# adalogger_featherwing.net
KiCad netlist of a schematic drawn in EAGLE
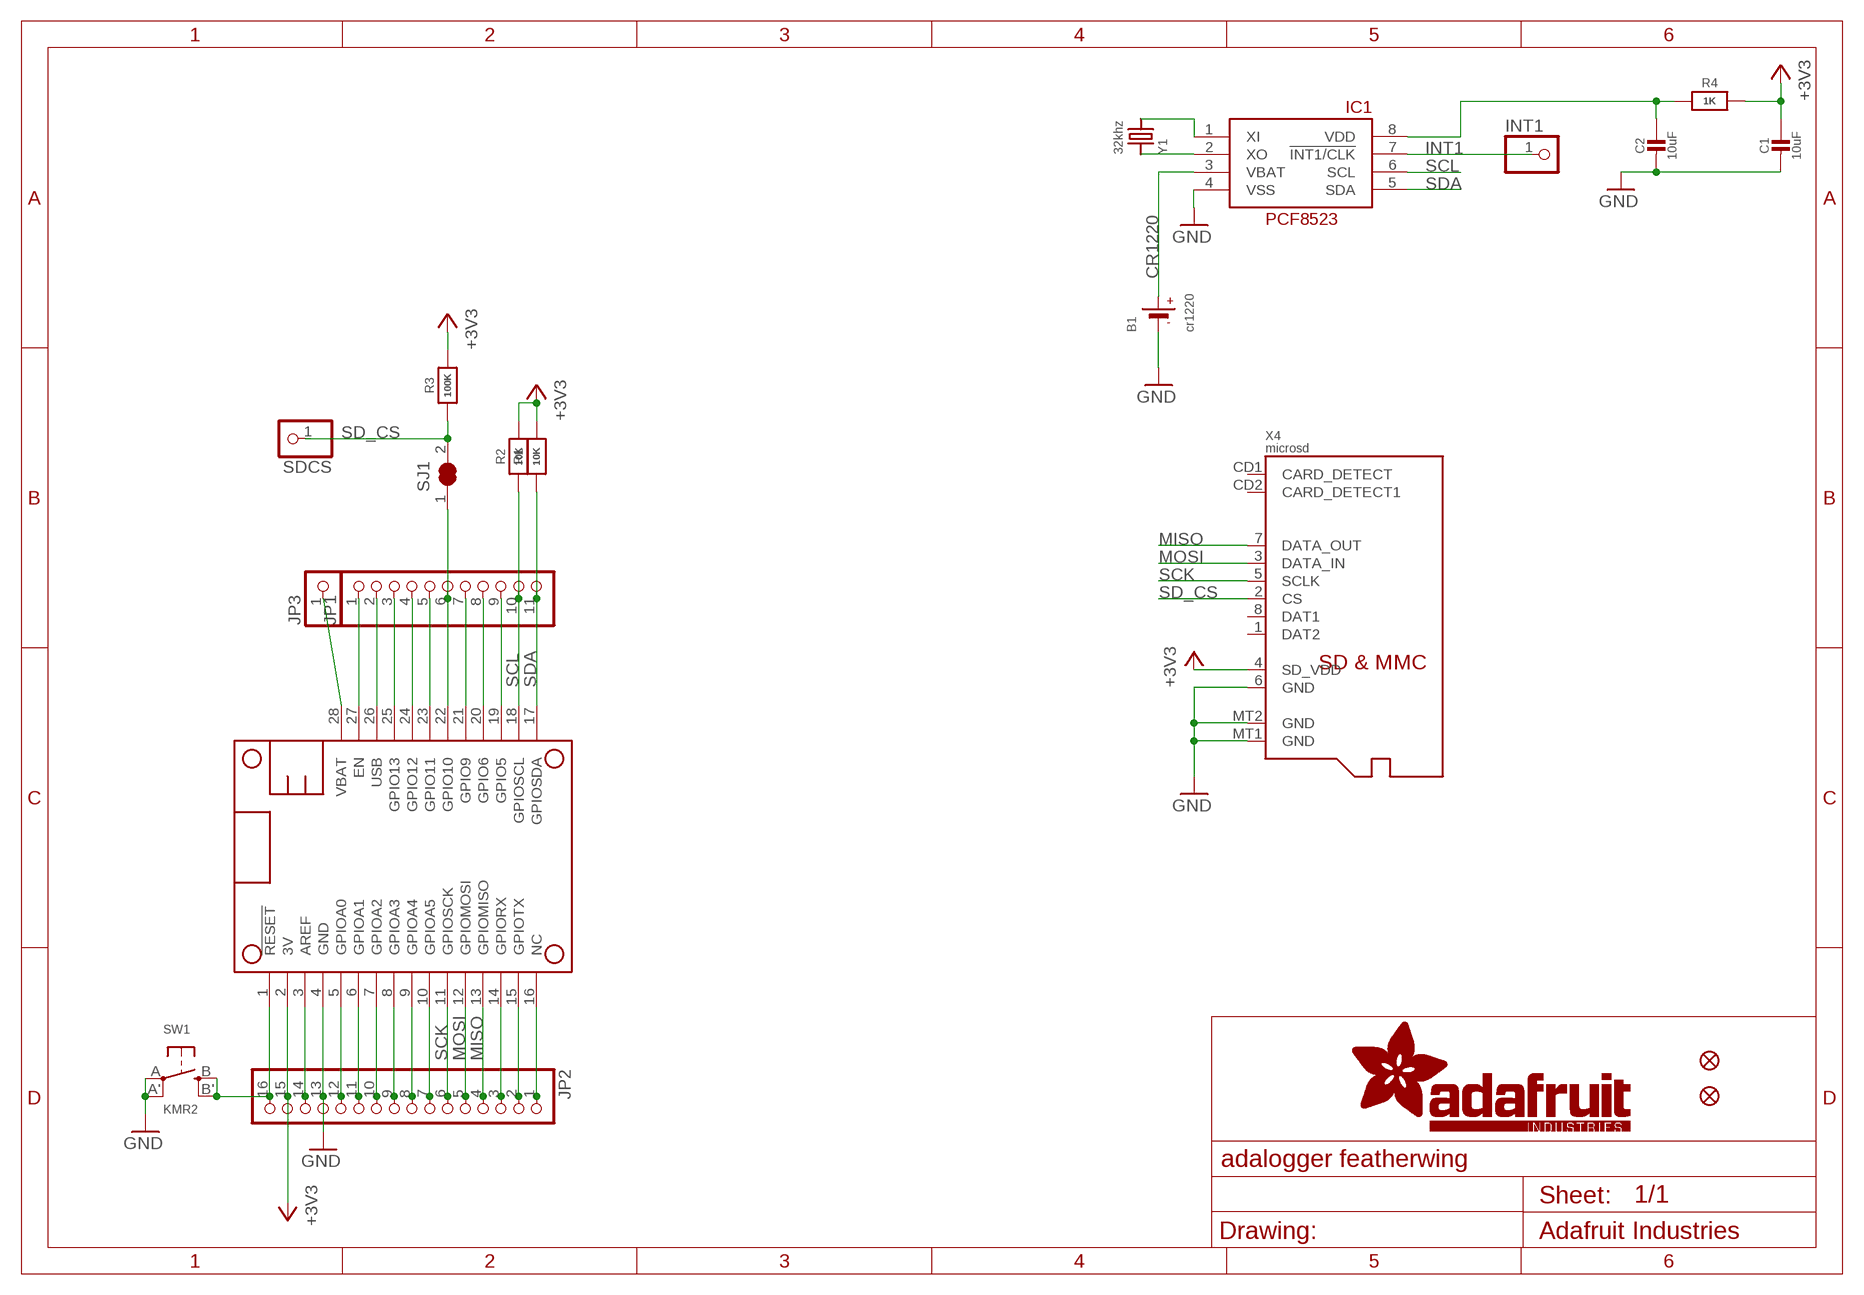
[diagram p0: schematic, sheet 1]

(export (version "E")
  (design (tool "Eeschema 10.0.6"))
  (components
    (comp (ref "B1")
      (value "cr1220")
      (footprint "eagle-import:CR1220-2")
      (libsource (lib "eagle-import") (part "BATTERYCR1220_2"))
    )
    (comp (ref "C1")
      (value "10uF")
      (footprint "eagle-import:0805-NO")
      (libsource (lib "eagle-import") (part "CAP_CERAMIC0805-NOOUTLINE"))
    )
    (comp (ref "C2")
      (value "10uF")
      (footprint "eagle-import:0805-NO")
      (libsource (lib "eagle-import") (part "CAP_CERAMIC0805-NOOUTLINE"))
    )
    (comp (ref "FID1")
      (value "FIDUCIAL\"\"")
      (footprint "eagle-import:FIDUCIAL_1MM")
      (libsource (lib "eagle-import") (part "FIDUCIAL{dblquote}{dblquote}"))
    )
    (comp (ref "FID2")
      (value "FIDUCIAL\"\"")
      (footprint "eagle-import:FIDUCIAL_1MM")
      (libsource (lib "eagle-import") (part "FIDUCIAL{dblquote}{dblquote}"))
    )
    (comp (ref "IC1")
      (value "RTC_PCF8523T")
      (footprint "eagle-import:SOIC8_150MIL")
      (libsource (lib "eagle-import") (part "RTC_PCF8523T"))
    )
    (comp (ref "INT1")
      (value "HEADER-1X1ROUND")
      (footprint "eagle-import:1X01_ROUND")
      (libsource (lib "eagle-import") (part "HEADER-1X1ROUND"))
    )
    (comp (ref "JP1")
      (value "HEADER-1X11")
      (footprint "eagle-import:1X11_ROUND")
      (libsource (lib "eagle-import") (part "HEADER-1X11"))
    )
    (comp (ref "JP2")
      (value "HEADER-1X16ROUND")
      (footprint "eagle-import:1X16_ROUND")
      (libsource (lib "eagle-import") (part "HEADER-1X16ROUND"))
    )
    (comp (ref "JP3")
      (value "HEADER-1X1ROUND")
      (footprint "eagle-import:1X01_ROUND")
      (libsource (lib "eagle-import") (part "HEADER-1X1ROUND"))
    )
    (comp (ref "MS1")
      (value "FEATHERWING_NODIM")
      (footprint "eagle-import:FEATHERWING_DIM")
      (libsource (lib "eagle-import") (part "FEATHERWING_NODIM"))
    )
    (comp (ref "R1")
      (value "10K")
      (footprint "eagle-import:0805-NO")
      (libsource (lib "eagle-import") (part "RESISTOR0805_NOOUTLINE"))
    )
    (comp (ref "R2")
      (value "10K")
      (footprint "eagle-import:0805-NO")
      (libsource (lib "eagle-import") (part "RESISTOR0805_NOOUTLINE"))
    )
    (comp (ref "R3")
      (value "100K")
      (footprint "eagle-import:0805-NO")
      (libsource (lib "eagle-import") (part "RESISTOR0805_NOOUTLINE"))
    )
    (comp (ref "R4")
      (value "1K")
      (footprint "eagle-import:0805-NO")
      (libsource (lib "eagle-import") (part "RESISTOR0805_NOOUTLINE"))
    )
    (comp (ref "SDCS")
      (value "HEADER-1X1ROUND")
      (footprint "eagle-import:1X01_ROUND")
      (libsource (lib "eagle-import") (part "HEADER-1X1ROUND"))
    )
    (comp (ref "SJ1")
      (value "SOLDERJUMPER_CLOSED")
      (footprint "eagle-import:SOLDERJUMPER_CLOSEDWIRE")
      (libsource (lib "eagle-import") (part "SOLDERJUMPER_CLOSED"))
    )
    (comp (ref "SW1")
      (value "KMR2")
      (footprint "eagle-import:BTN_KMR2_4.6X2.8")
      (libsource (lib "eagle-import") (part "SWITCH_TACT_SMT4.6X2.8"))
    )
    (comp (ref "X4")
      (value "microsd")
      (footprint "eagle-import:MICROSD")
      (libsource (lib "eagle-import") (part "MICROSD"))
    )
    (comp (ref "Y1")
      (value "32khz")
      (footprint "eagle-import:CRYSTAL_8X3.8")
      (libsource (lib "eagle-import") (part "CRYSTAL8.0X3.8"))
    )
  )
  (nets
    (net (code "1") (name "+3V3") (class "Default")
      (node (ref "C1") (pin "1") (pinfunction "1_1") (pintype "passive"))
      (node (ref "JP2") (pin "15") (pinfunction "15_15") (pintype "passive"))
      (node (ref "MS1") (pin "2") (pinfunction "3V_2") (pintype "power_in"))
      (node (ref "R1") (pin "2") (pinfunction "2_2") (pintype "passive"))
      (node (ref "R2") (pin "2") (pinfunction "2_2") (pintype "passive"))
      (node (ref "R3") (pin "2") (pinfunction "2_2") (pintype "passive"))
      (node (ref "R4") (pin "1") (pinfunction "1_1") (pintype "passive"))
      (node (ref "X4") (pin "4") (pinfunction "SD_VDD_4") (pintype "power_in"))
    )
    (net (code "2") (name "/CR1220") (class "Default")
      (node (ref "B1") (pin "+") (pinfunction "+_+") (pintype "passive"))
      (node (ref "IC1") (pin "3") (pinfunction "VBAT_3") (pintype "power_in"))
    )
    (net (code "3") (name "/INT1") (class "Default")
      (node (ref "IC1") (pin "7") (pinfunction "~{INT1/CLK}_7") (pintype "output"))
      (node (ref "INT1") (pin "1") (pinfunction "1_1") (pintype "passive"))
    )
    (net (code "4") (name "/MISO") (class "Default")
      (node (ref "JP2") (pin "4") (pinfunction "4_4") (pintype "passive"))
      (node (ref "MS1") (pin "13") (pinfunction "GPIOMISO_13") (pintype "bidirectional"))
      (node (ref "X4") (pin "7") (pinfunction "DATA_OUT_7") (pintype "output"))
    )
    (net (code "5") (name "/MOSI") (class "Default")
      (node (ref "JP2") (pin "5") (pinfunction "5_5") (pintype "passive"))
      (node (ref "MS1") (pin "12") (pinfunction "GPIOMOSI_12") (pintype "bidirectional"))
      (node (ref "X4") (pin "3") (pinfunction "DATA_IN_3") (pintype "input"))
    )
    (net (code "6") (name "/SCK") (class "Default")
      (node (ref "JP2") (pin "6") (pinfunction "6_6") (pintype "passive"))
      (node (ref "MS1") (pin "11") (pinfunction "GPIOSCK_11") (pintype "bidirectional"))
      (node (ref "X4") (pin "5") (pinfunction "SCLK_5") (pintype "input"))
    )
    (net (code "7") (name "/SCL") (class "Default")
      (node (ref "IC1") (pin "6") (pinfunction "SCL_6") (pintype "bidirectional"))
      (node (ref "JP1") (pin "10") (pinfunction "10_10") (pintype "passive"))
      (node (ref "MS1") (pin "18") (pinfunction "GPIOSCL_18") (pintype "bidirectional"))
      (node (ref "R2") (pin "1") (pinfunction "1_1") (pintype "passive"))
    )
    (net (code "8") (name "/SDA") (class "Default")
      (node (ref "IC1") (pin "5") (pinfunction "SDA_5") (pintype "bidirectional"))
      (node (ref "JP1") (pin "11") (pinfunction "11_11") (pintype "passive"))
      (node (ref "MS1") (pin "17") (pinfunction "GPIOSDA_17") (pintype "bidirectional"))
      (node (ref "R1") (pin "1") (pinfunction "1_1") (pintype "passive"))
    )
    (net (code "9") (name "/SD_CS") (class "Default")
      (node (ref "R3") (pin "1") (pinfunction "1_1") (pintype "passive"))
      (node (ref "SDCS") (pin "1") (pinfunction "1_1") (pintype "passive"))
      (node (ref "SJ1") (pin "2") (pinfunction "2_2") (pintype "passive"))
      (node (ref "X4") (pin "2") (pinfunction "CS_2") (pintype "input"))
    )
    (net (code "10") (name "GND") (class "Default")
      (node (ref "B1") (pin "-") (pinfunction "-_-") (pintype "passive"))
      (node (ref "C1") (pin "2") (pinfunction "2_2") (pintype "passive"))
      (node (ref "C2") (pin "2") (pinfunction "2_2") (pintype "passive"))
      (node (ref "IC1") (pin "4") (pinfunction "VSS_4") (pintype "power_in"))
      (node (ref "JP2") (pin "13") (pinfunction "13_13") (pintype "passive"))
      (node (ref "MS1") (pin "4") (pinfunction "GND_4") (pintype "power_in"))
      (node (ref "SW1") (pin "A") (pinfunction "P_A") (pintype "passive"))
      (node (ref "SW1") (pin "A'") (pinfunction "P1_A'") (pintype "passive"))
      (node (ref "X4") (pin "6") (pinfunction "GND_6") (pintype "power_in"))
      (node (ref "X4") (pin "MT1") (pinfunction "GND_MT1") (pintype "power_in"))
      (node (ref "X4") (pin "MT2") (pinfunction "GND_MT2") (pintype "power_in"))
    )
    (net (code "11") (name "Net-(IC1-VDD)") (class "Default")
      (node (ref "C2") (pin "1") (pinfunction "1_1") (pintype "passive"))
      (node (ref "IC1") (pin "8") (pinfunction "VDD_8") (pintype "power_in"))
      (node (ref "R4") (pin "2") (pinfunction "2_2") (pintype "passive"))
    )
    (net (code "12") (name "Net-(IC1-XI)") (class "Default")
      (node (ref "IC1") (pin "1") (pinfunction "XI_1") (pintype "input"))
      (node (ref "Y1") (pin "P$4") (pinfunction "2_P$4") (pintype "passive"))
    )
    (net (code "13") (name "Net-(IC1-XO)") (class "Default")
      (node (ref "IC1") (pin "2") (pinfunction "XO_2") (pintype "output"))
      (node (ref "Y1") (pin "P$1") (pinfunction "1_P$1") (pintype "passive"))
    )
    (net (code "14") (name "Net-(MS1-AREF)") (class "Default")
      (node (ref "JP2") (pin "14") (pinfunction "14_14") (pintype "passive"))
      (node (ref "MS1") (pin "3") (pinfunction "AREF_3") (pintype "passive"))
    )
    (net (code "15") (name "Net-(MS1-EN)") (class "Default")
      (node (ref "JP1") (pin "1") (pinfunction "1_1") (pintype "passive"))
      (node (ref "MS1") (pin "27") (pinfunction "EN_27") (pintype "passive"))
    )
    (net (code "16") (name "Net-(MS1-GPIO5)") (class "Default")
      (node (ref "JP1") (pin "9") (pinfunction "9_9") (pintype "passive"))
      (node (ref "MS1") (pin "19") (pinfunction "GPIO5_19") (pintype "bidirectional"))
    )
    (net (code "17") (name "Net-(MS1-GPIO6)") (class "Default")
      (node (ref "JP1") (pin "8") (pinfunction "8_8") (pintype "passive"))
      (node (ref "MS1") (pin "20") (pinfunction "GPIO6_20") (pintype "bidirectional"))
    )
    (net (code "18") (name "Net-(MS1-GPIO9)") (class "Default")
      (node (ref "JP1") (pin "7") (pinfunction "7_7") (pintype "passive"))
      (node (ref "MS1") (pin "21") (pinfunction "GPIO9_21") (pintype "bidirectional"))
    )
    (net (code "19") (name "Net-(MS1-GPIO10)") (class "Default")
      (node (ref "JP1") (pin "6") (pinfunction "6_6") (pintype "passive"))
      (node (ref "MS1") (pin "22") (pinfunction "GPIO10_22") (pintype "bidirectional"))
      (node (ref "SJ1") (pin "1") (pinfunction "1_1") (pintype "passive"))
    )
    (net (code "20") (name "Net-(MS1-GPIO11)") (class "Default")
      (node (ref "JP1") (pin "5") (pinfunction "5_5") (pintype "passive"))
      (node (ref "MS1") (pin "23") (pinfunction "GPIO11_23") (pintype "bidirectional"))
    )
    (net (code "21") (name "Net-(MS1-GPIO12)") (class "Default")
      (node (ref "JP1") (pin "4") (pinfunction "4_4") (pintype "passive"))
      (node (ref "MS1") (pin "24") (pinfunction "GPIO12_24") (pintype "bidirectional"))
    )
    (net (code "22") (name "Net-(MS1-GPIO13)") (class "Default")
      (node (ref "JP1") (pin "3") (pinfunction "3_3") (pintype "passive"))
      (node (ref "MS1") (pin "25") (pinfunction "GPIO13_25") (pintype "bidirectional"))
    )
    (net (code "23") (name "Net-(MS1-GPIOA0)") (class "Default")
      (node (ref "JP2") (pin "12") (pinfunction "12_12") (pintype "passive"))
      (node (ref "MS1") (pin "5") (pinfunction "GPIOA0_5") (pintype "bidirectional"))
    )
    (net (code "24") (name "Net-(MS1-GPIOA1)") (class "Default")
      (node (ref "JP2") (pin "11") (pinfunction "11_11") (pintype "passive"))
      (node (ref "MS1") (pin "6") (pinfunction "GPIOA1_6") (pintype "bidirectional"))
    )
    (net (code "25") (name "Net-(MS1-GPIOA2)") (class "Default")
      (node (ref "JP2") (pin "10") (pinfunction "10_10") (pintype "passive"))
      (node (ref "MS1") (pin "7") (pinfunction "GPIOA2_7") (pintype "bidirectional"))
    )
    (net (code "26") (name "Net-(MS1-GPIOA3)") (class "Default")
      (node (ref "JP2") (pin "9") (pinfunction "9_9") (pintype "passive"))
      (node (ref "MS1") (pin "8") (pinfunction "GPIOA3_8") (pintype "bidirectional"))
    )
    (net (code "27") (name "Net-(MS1-GPIOA4)") (class "Default")
      (node (ref "JP2") (pin "8") (pinfunction "8_8") (pintype "passive"))
      (node (ref "MS1") (pin "9") (pinfunction "GPIOA4_9") (pintype "bidirectional"))
    )
    (net (code "28") (name "Net-(MS1-GPIOA5)") (class "Default")
      (node (ref "JP2") (pin "7") (pinfunction "7_7") (pintype "passive"))
      (node (ref "MS1") (pin "10") (pinfunction "GPIOA5_10") (pintype "bidirectional"))
    )
    (net (code "29") (name "Net-(MS1-GPIORX)") (class "Default")
      (node (ref "JP2") (pin "3") (pinfunction "3_3") (pintype "passive"))
      (node (ref "MS1") (pin "14") (pinfunction "GPIORX_14") (pintype "bidirectional"))
    )
    (net (code "30") (name "Net-(MS1-GPIOTX)") (class "Default")
      (node (ref "JP2") (pin "2") (pinfunction "2_2") (pintype "passive"))
      (node (ref "MS1") (pin "15") (pinfunction "GPIOTX_15") (pintype "bidirectional"))
    )
    (net (code "31") (name "Net-(MS1-NC)") (class "Default")
      (node (ref "JP2") (pin "1") (pinfunction "1_1") (pintype "passive"))
      (node (ref "MS1") (pin "16") (pinfunction "NC_16") (pintype "passive"))
    )
    (net (code "32") (name "Net-(MS1-USB)") (class "Default")
      (node (ref "JP1") (pin "2") (pinfunction "2_2") (pintype "passive"))
      (node (ref "MS1") (pin "26") (pinfunction "USB_26") (pintype "power_in"))
    )
    (net (code "33") (name "Net-(MS1-VBAT)") (class "Default")
      (node (ref "JP3") (pin "1") (pinfunction "1_1") (pintype "passive"))
      (node (ref "MS1") (pin "28") (pinfunction "VBAT_28") (pintype "power_in"))
    )
    (net (code "34") (name "Net-(MS1-~{RESET})") (class "Default")
      (node (ref "JP2") (pin "16") (pinfunction "16_16") (pintype "passive"))
      (node (ref "MS1") (pin "1") (pinfunction "~{RESET}_1") (pintype "input"))
      (node (ref "SW1") (pin "B") (pinfunction "S_B") (pintype "passive"))
      (node (ref "SW1") (pin "B'") (pinfunction "S1_B'") (pintype "passive"))
    )
    (net (code "35") (name "unconnected-(X4-CARD_DETECT-PadCD1)") (class "Default")
      (node (ref "X4") (pin "CD1") (pinfunction "CARD_DETECT_CD1") (pintype "passive"))
    )
    (net (code "36") (name "unconnected-(X4-CARD_DETECT1-PadCD2)") (class "Default")
      (node (ref "X4") (pin "CD2") (pinfunction "CARD_DETECT1_CD2") (pintype "passive"))
    )
    (net (code "37") (name "unconnected-(X4-DAT1-Pad8)") (class "Default")
      (node (ref "X4") (pin "8") (pinfunction "DAT1_8") (pintype "bidirectional"))
    )
    (net (code "38") (name "unconnected-(X4-DAT2-Pad1)") (class "Default")
      (node (ref "X4") (pin "1") (pinfunction "DAT2_1") (pintype "bidirectional"))
    )
  )
)
